# laser_ontvanger.net
KiCad netlist of a schematic drawn in EAGLE
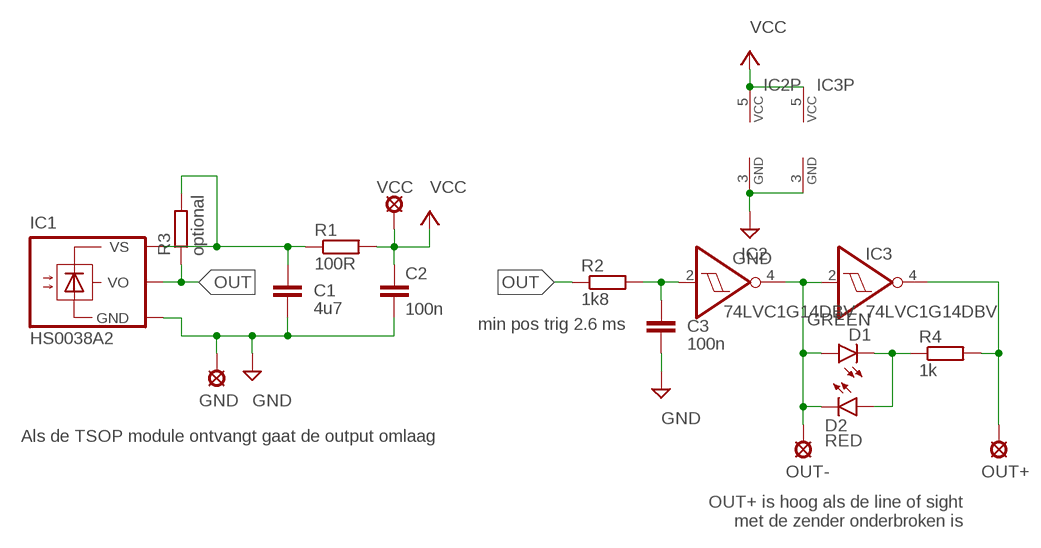
[diagram p0: schematic, sheet 1]

(export (version "E")
  (design (tool "Eeschema 10.0.6"))
  (components
    (comp (ref "C1")
      (value "4u7")
      (footprint "eagle-import:C0805")
      (libsource (lib "eagle-import") (part "C-EUC0805"))
    )
    (comp (ref "C2")
      (value "100n")
      (footprint "eagle-import:C0805")
      (libsource (lib "eagle-import") (part "C-EUC0805"))
    )
    (comp (ref "C3")
      (value "100n")
      (footprint "eagle-import:C0805")
      (libsource (lib "eagle-import") (part "C-EUC0805"))
    )
    (comp (ref "D1")
      (value "GREEN")
      (footprint "eagle-import:CHIP-LED0805")
      (libsource (lib "eagle-import") (part "LEDCHIP-LED0805"))
    )
    (comp (ref "D2")
      (value "RED")
      (footprint "eagle-import:CHIP-LED0805")
      (libsource (lib "eagle-import") (part "LEDCHIP-LED0805"))
    )
    (comp (ref "GND")
      (value "LSP10")
      (footprint "eagle-import:LSP10")
      (libsource (lib "eagle-import") (part "LSP10"))
    )
    (comp (ref "IC1")
      (value "HS0038A2")
      (footprint "eagle-import:TSOP17_TB1")
      (libsource (lib "eagle-import") (part "HS0038A2"))
    )
    (comp (ref "IC2")
      (value "74LVC1G14DBV")
      (footprint "eagle-import:SOT23-5")
      (libsource (lib "eagle-import") (part "741G14DBVLVC"))
    )
    (comp (ref "IC3")
      (value "74LVC1G14DBV")
      (footprint "eagle-import:SOT23-5")
      (libsource (lib "eagle-import") (part "741G14DBVLVC"))
    )
    (comp (ref "OUT+")
      (value "LSP10")
      (footprint "eagle-import:LSP10")
      (libsource (lib "eagle-import") (part "LSP10"))
    )
    (comp (ref "OUT-")
      (value "LSP10")
      (footprint "eagle-import:LSP10")
      (libsource (lib "eagle-import") (part "LSP10"))
    )
    (comp (ref "R1")
      (value "100R")
      (footprint "eagle-import:R0805")
      (libsource (lib "eagle-import") (part "R-EU_R0805"))
    )
    (comp (ref "R2")
      (value "1k8")
      (footprint "eagle-import:R0805")
      (libsource (lib "eagle-import") (part "R-EU_R0805"))
    )
    (comp (ref "R3")
      (value "optional")
      (footprint "eagle-import:R0805")
      (libsource (lib "eagle-import") (part "R-EU_R0805"))
    )
    (comp (ref "R4")
      (value "1k")
      (footprint "eagle-import:R0805")
      (libsource (lib "eagle-import") (part "R-EU_R0805"))
    )
    (comp (ref "VCC")
      (value "LSP10")
      (footprint "eagle-import:LSP10")
      (libsource (lib "eagle-import") (part "LSP10"))
    )
  )
  (nets
    (net (code "1") (name "GND") (class "Default")
      (node (ref "C1") (pin "2") (pinfunction "2_2") (pintype "passive"))
      (node (ref "C2") (pin "2") (pinfunction "2_2") (pintype "passive"))
      (node (ref "C3") (pin "2") (pinfunction "2_2") (pintype "passive"))
      (node (ref "GND") (pin "MP") (pinfunction "MP_MP") (pintype "passive"))
      (node (ref "IC1") (pin "GND") (pinfunction "GND_GND") (pintype "power_in"))
      (node (ref "IC2") (pin "3") (pinfunction "GND_3") (pintype "power_in"))
      (node (ref "IC3") (pin "3") (pinfunction "GND_3") (pintype "power_in"))
    )
    (net (code "2") (name "Net-(C1-Pad1)") (class "Default")
      (node (ref "C1") (pin "1") (pinfunction "1_1") (pintype "passive"))
      (node (ref "IC1") (pin "VS") (pinfunction "VS_VS") (pintype "power_in"))
      (node (ref "R1") (pin "1") (pinfunction "1_1") (pintype "passive"))
      (node (ref "R3") (pin "2") (pinfunction "2_2") (pintype "passive"))
    )
    (net (code "3") (name "Net-(D1-PadC)") (class "Default")
      (node (ref "D1") (pin "C") (pinfunction "C_C") (pintype "passive"))
      (node (ref "D2") (pin "A") (pinfunction "A_A") (pintype "passive"))
      (node (ref "R4") (pin "1") (pinfunction "1_1") (pintype "passive"))
    )
    (net (code "4") (name "Net-(IC2A-I)") (class "Default")
      (node (ref "C3") (pin "1") (pinfunction "1_1") (pintype "passive"))
      (node (ref "IC2") (pin "2") (pinfunction "I_2") (pintype "input"))
      (node (ref "R2") (pin "2") (pinfunction "2_2") (pintype "passive"))
    )
    (net (code "5") (name "Net-(IC2A-O)") (class "Default")
      (node (ref "D1") (pin "A") (pinfunction "A_A") (pintype "passive"))
      (node (ref "D2") (pin "C") (pinfunction "C_C") (pintype "passive"))
      (node (ref "IC2") (pin "4") (pinfunction "O_4") (pintype "output"))
      (node (ref "IC3") (pin "2") (pinfunction "I_2") (pintype "input"))
      (node (ref "OUT-") (pin "MP") (pinfunction "MP_MP") (pintype "passive"))
    )
    (net (code "6") (name "Net-(IC3A-O)") (class "Default")
      (node (ref "IC3") (pin "4") (pinfunction "O_4") (pintype "output"))
      (node (ref "OUT+") (pin "MP") (pinfunction "MP_MP") (pintype "passive"))
      (node (ref "R4") (pin "2") (pinfunction "2_2") (pintype "passive"))
    )
    (net (code "7") (name "OUT") (class "Default")
      (node (ref "IC1") (pin "VO") (pinfunction "VO_VO") (pintype "open_collector"))
      (node (ref "R2") (pin "1") (pinfunction "1_1") (pintype "passive"))
      (node (ref "R3") (pin "1") (pinfunction "1_1") (pintype "passive"))
    )
    (net (code "8") (name "VCC") (class "Default")
      (node (ref "C2") (pin "1") (pinfunction "1_1") (pintype "passive"))
      (node (ref "IC2") (pin "5") (pinfunction "VCC_5") (pintype "power_in"))
      (node (ref "IC3") (pin "5") (pinfunction "VCC_5") (pintype "power_in"))
      (node (ref "R1") (pin "2") (pinfunction "2_2") (pintype "passive"))
      (node (ref "VCC") (pin "MP") (pinfunction "MP_MP") (pintype "passive"))
    )
  )
)
